# io-pack-3-4.net
KiCad netlist of a schematic drawn in EAGLE
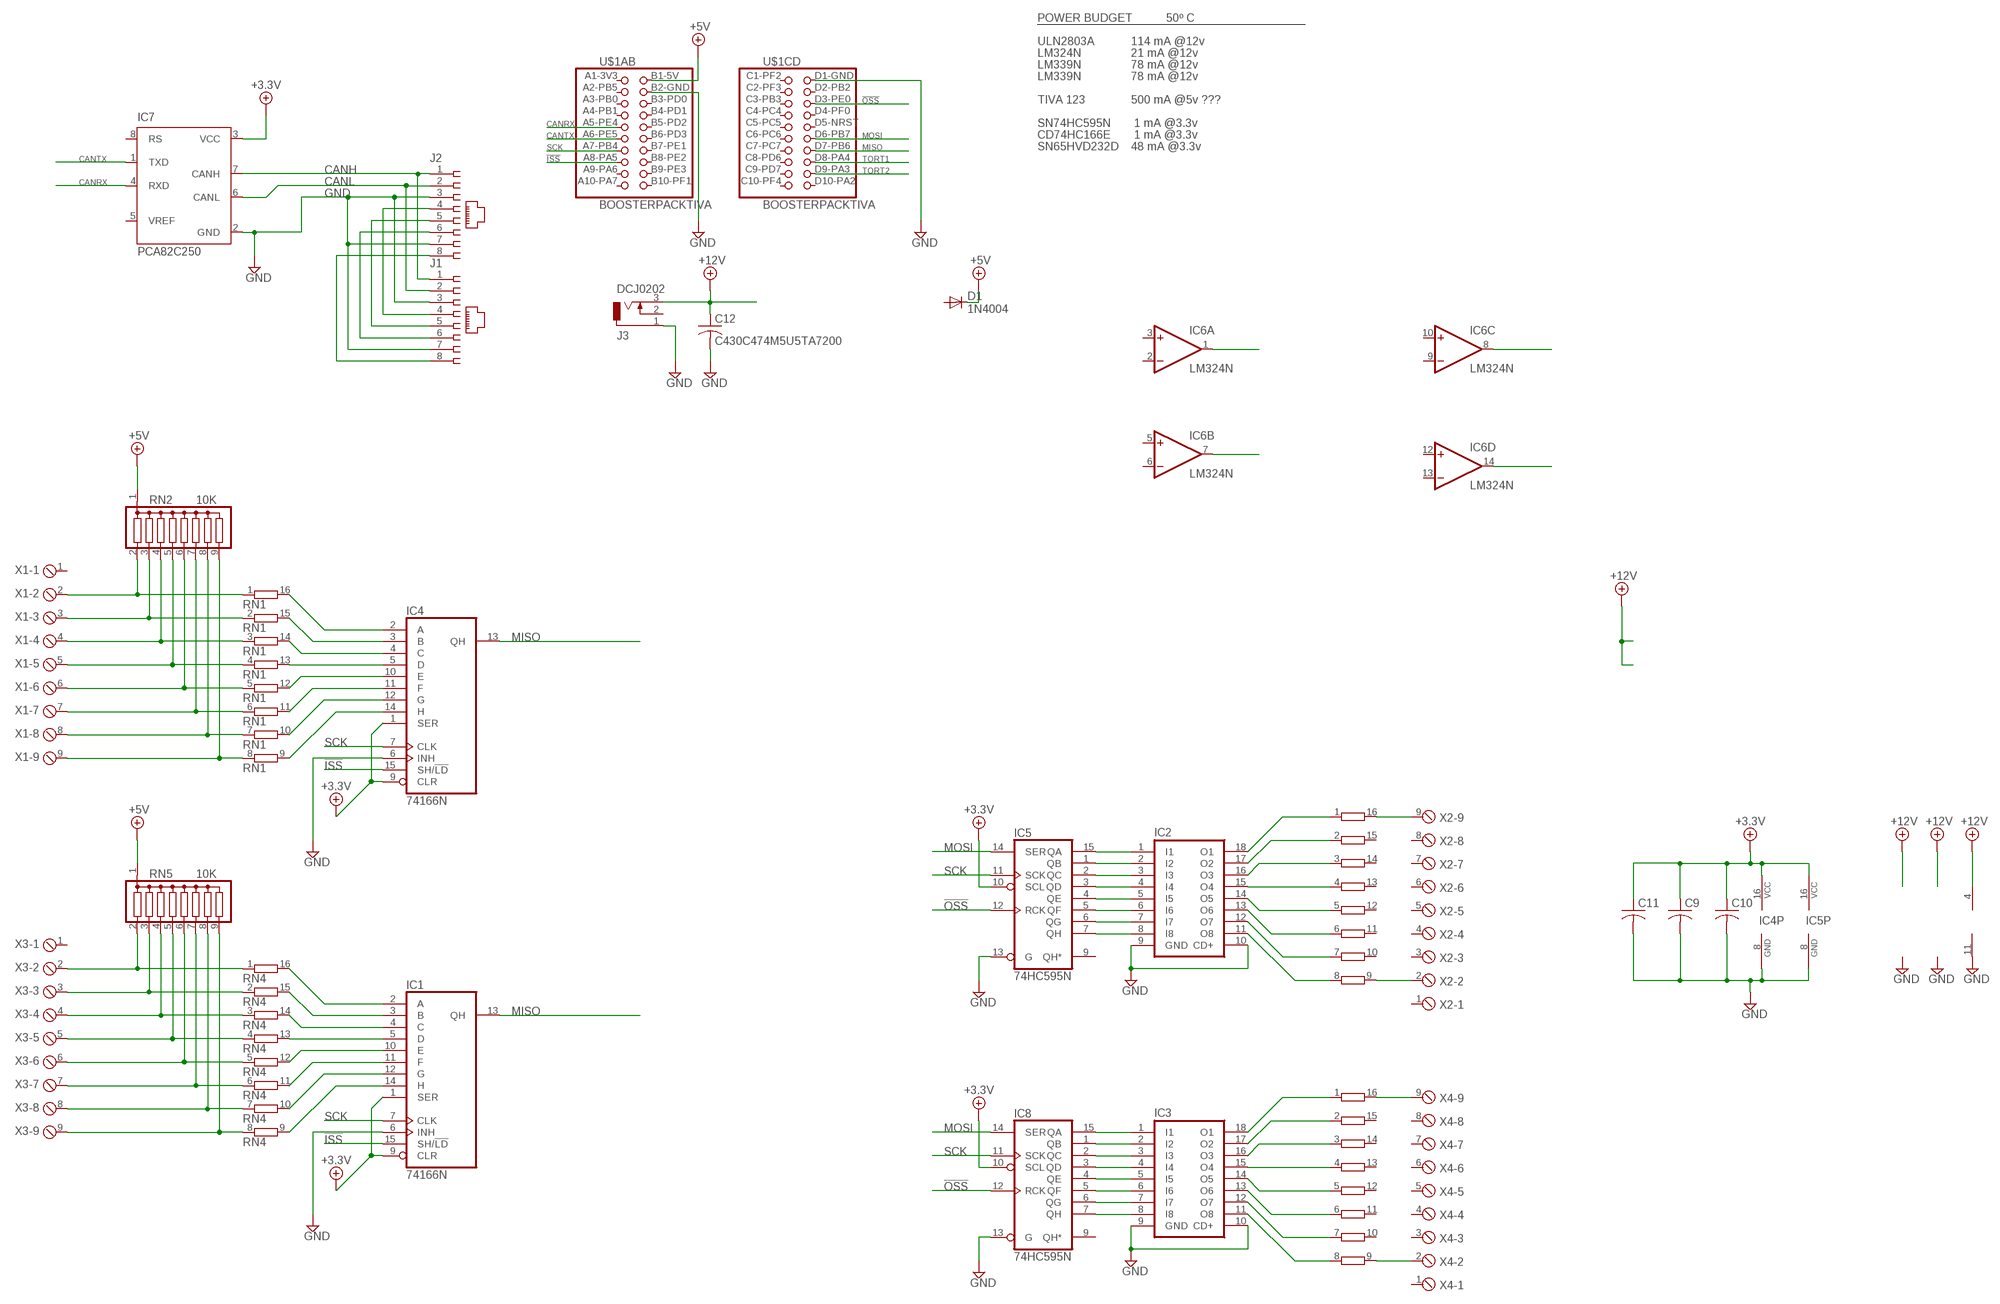
[diagram p0: schematic, sheet 1]

(export (version "E")
  (design (tool "Eeschema 10.0.6"))
  (components
    (comp (ref "C9")
      (value "C-US050-025X075")
      (footprint "eagle-import:C050-025X075")
      (libsource (lib "eagle-import") (part "C-US050-025X075"))
    )
    (comp (ref "C10")
      (value "C-US050-025X075")
      (footprint "eagle-import:C050-025X075")
      (libsource (lib "eagle-import") (part "C-US050-025X075"))
    )
    (comp (ref "C11")
      (value "C-US050-025X075")
      (footprint "eagle-import:C050-025X075")
      (libsource (lib "eagle-import") (part "C-US050-025X075"))
    )
    (comp (ref "C12")
      (value "C430C474M5U5TA7200")
      (footprint "eagle-import:C075-032X103")
      (libsource (lib "eagle-import") (part "C-US075-032X103"))
    )
    (comp (ref "D1")
      (value "1N4004")
      (footprint "eagle-import:DO41-10")
      (libsource (lib "eagle-import") (part "1N4004"))
    )
    (comp (ref "IC1")
      (value "74166N")
      (footprint "eagle-import:DIL16")
      (libsource (lib "eagle-import") (part "74166N"))
    )
    (comp (ref "IC2")
      (value "ULN2803A")
      (footprint "eagle-import:DIL18")
      (libsource (lib "eagle-import") (part "ULN2803A"))
    )
    (comp (ref "IC3")
      (value "ULN2803A")
      (footprint "eagle-import:DIL18")
      (libsource (lib "eagle-import") (part "ULN2803A"))
    )
    (comp (ref "IC4")
      (value "74166N")
      (footprint "eagle-import:DIL16")
      (libsource (lib "eagle-import") (part "74166N"))
    )
    (comp (ref "IC5")
      (value "74HC595N")
      (footprint "eagle-import:DIL16")
      (libsource (lib "eagle-import") (part "74595NLS"))
    )
    (comp (ref "IC6")
      (value "LM324N")
      (footprint "eagle-import:DIL14")
      (libsource (lib "eagle-import") (part "LM324N"))
    )
    (comp (ref "IC7")
      (value "PCA82C250")
      (footprint "eagle-import:DIL08")
      (libsource (lib "eagle-import") (part "PCA82C250"))
    )
    (comp (ref "IC8")
      (value "74HC595N")
      (footprint "eagle-import:DIL16")
      (libsource (lib "eagle-import") (part "74595NLS"))
    )
    (comp (ref "J1")
      (value "555164-1")
      (footprint "eagle-import:555164-1")
      (libsource (lib "eagle-import") (part "555164-1"))
    )
    (comp (ref "J2")
      (value "555164-1")
      (footprint "eagle-import:555164-1")
      (libsource (lib "eagle-import") (part "555164-1"))
    )
    (comp (ref "J3")
      (value "DCJ0202")
      (footprint "eagle-import:DCJ0202")
      (libsource (lib "eagle-import") (part "DCJ0202"))
    )
    (comp (ref "RN1")
      (value "8R-P")
      (footprint "eagle-import:DIL16")
      (libsource (lib "eagle-import") (part "8R-P"))
    )
    (comp (ref "RN2")
      (value "10K")
      (footprint "eagle-import:SIL9")
      (libsource (lib "eagle-import") (part "G08R"))
    )
    (comp (ref "RN3")
      (value "8R-P")
      (footprint "eagle-import:DIL16")
      (libsource (lib "eagle-import") (part "8R-P"))
    )
    (comp (ref "RN4")
      (value "8R-P")
      (footprint "eagle-import:DIL16")
      (libsource (lib "eagle-import") (part "8R-P"))
    )
    (comp (ref "RN5")
      (value "10K")
      (footprint "eagle-import:SIL9")
      (libsource (lib "eagle-import") (part "G08R"))
    )
    (comp (ref "RN6")
      (value "8R-P")
      (footprint "eagle-import:DIL16")
      (libsource (lib "eagle-import") (part "8R-P"))
    )
    (comp (ref "U$1")
      (value "BOOSTERPACKTIVA")
      (footprint "eagle-import:BOOSTERPACK-TIVA")
      (libsource (lib "eagle-import") (part "BOOSTERPACKTIVA"))
    )
    (comp (ref "X1")
      (value "MPT9")
      (footprint "eagle-import:9POL254")
      (libsource (lib "eagle-import") (part "MPT9"))
    )
    (comp (ref "X2")
      (value "MPT9")
      (footprint "eagle-import:9POL254")
      (libsource (lib "eagle-import") (part "MPT9"))
    )
    (comp (ref "X3")
      (value "MPT9")
      (footprint "eagle-import:9POL254")
      (libsource (lib "eagle-import") (part "MPT9"))
    )
    (comp (ref "X4")
      (value "MPT9")
      (footprint "eagle-import:9POL254")
      (libsource (lib "eagle-import") (part "MPT9"))
    )
  )
  (nets
    (net (code "1") (name "+3.3V") (class "Default")
      (node (ref "C10") (pin "1") (pinfunction "1_1") (pintype "passive"))
      (node (ref "C11") (pin "1") (pinfunction "1_1") (pintype "passive"))
      (node (ref "C9") (pin "1") (pinfunction "1_1") (pintype "passive"))
      (node (ref "IC1") (pin "1") (pinfunction "SER_1") (pintype "input"))
      (node (ref "IC1") (pin "9") (pinfunction "CLR_9") (pintype "input"))
      (node (ref "IC4") (pin "1") (pinfunction "SER_1") (pintype "input"))
      (node (ref "IC4") (pin "16") (pinfunction "VCC_16") (pintype "power_in"))
      (node (ref "IC4") (pin "9") (pinfunction "CLR_9") (pintype "input"))
      (node (ref "IC5") (pin "10") (pinfunction "SCL_10") (pintype "input"))
      (node (ref "IC5") (pin "16") (pinfunction "VCC_16") (pintype "power_in"))
      (node (ref "IC7") (pin "3") (pinfunction "VCC_3") (pintype "power_in"))
      (node (ref "IC8") (pin "10") (pinfunction "SCL_10") (pintype "input"))
    )
    (net (code "2") (name "+5V") (class "Default")
      (node (ref "D1") (pin "C") (pinfunction "C_C") (pintype "passive"))
      (node (ref "RN2") (pin "1") (pinfunction "1_1") (pintype "passive"))
      (node (ref "RN5") (pin "1") (pinfunction "1_1") (pintype "passive"))
      (node (ref "U$1") (pin "B1-5V") (pinfunction "2_B1-5V") (pintype "passive"))
    )
    (net (code "3") (name "+12V") (class "Default")
      (node (ref "C12") (pin "1") (pinfunction "1_1") (pintype "passive"))
      (node (ref "IC6") (pin "4") (pinfunction "V+_4") (pintype "power_in"))
      (node (ref "J3") (pin "3") (pinfunction "3_3") (pintype "passive"))
    )
    (net (code "4") (name "/CANH") (class "Default")
      (node (ref "IC7") (pin "7") (pinfunction "CANH_7") (pintype "bidirectional"))
      (node (ref "J1") (pin "1") (pinfunction "1_1") (pintype "passive"))
      (node (ref "J2") (pin "1") (pinfunction "1_1") (pintype "passive"))
    )
    (net (code "5") (name "/CANL") (class "Default")
      (node (ref "IC7") (pin "6") (pinfunction "CANL_6") (pintype "bidirectional"))
      (node (ref "J1") (pin "2") (pinfunction "2_2") (pintype "passive"))
      (node (ref "J2") (pin "2") (pinfunction "2_2") (pintype "passive"))
    )
    (net (code "6") (name "/CANRX") (class "Default")
      (node (ref "IC7") (pin "4") (pinfunction "RXD_4") (pintype "output"))
      (node (ref "U$1") (pin "A5-PE4") (pinfunction "9_A5-PE4") (pintype "passive"))
    )
    (net (code "7") (name "/CANTX") (class "Default")
      (node (ref "IC7") (pin "1") (pinfunction "TXD_1") (pintype "input"))
      (node (ref "U$1") (pin "A6-PE5") (pinfunction "11_A6-PE5") (pintype "passive"))
    )
    (net (code "8") (name "/MISO") (class "Default")
      (node (ref "IC1") (pin "13") (pinfunction "QH_13") (pintype "output"))
      (node (ref "IC4") (pin "13") (pinfunction "QH_13") (pintype "output"))
      (node (ref "U$1") (pin "D7-PB6") (pinfunction "14_D7-PB6") (pintype "passive"))
    )
    (net (code "9") (name "/MOSI") (class "Default")
      (node (ref "IC5") (pin "14") (pinfunction "SER_14") (pintype "input"))
      (node (ref "IC8") (pin "14") (pinfunction "SER_14") (pintype "input"))
      (node (ref "U$1") (pin "D6-PB7") (pinfunction "12_D6-PB7") (pintype "passive"))
    )
    (net (code "10") (name "/SCK") (class "Default")
      (node (ref "IC1") (pin "7") (pinfunction "CLK_7") (pintype "input"))
      (node (ref "IC4") (pin "7") (pinfunction "CLK_7") (pintype "input"))
      (node (ref "IC5") (pin "11") (pinfunction "SCK_11") (pintype "input"))
      (node (ref "IC8") (pin "11") (pinfunction "SCK_11") (pintype "input"))
      (node (ref "U$1") (pin "A7-PB4") (pinfunction "13_A7-PB4") (pintype "passive"))
    )
    (net (code "11") (name "/TORT1") (class "Default")
      (node (ref "U$1") (pin "D8-PA4") (pinfunction "16_D8-PA4") (pintype "passive"))
    )
    (net (code "12") (name "/TORT2") (class "Default")
      (node (ref "U$1") (pin "D9-PA3") (pinfunction "18_D9-PA3") (pintype "passive"))
    )
    (net (code "13") (name "/~{ISS}") (class "Default")
      (node (ref "IC1") (pin "15") (pinfunction "SH/~{LD}_15") (pintype "input"))
      (node (ref "IC4") (pin "15") (pinfunction "SH/~{LD}_15") (pintype "input"))
      (node (ref "U$1") (pin "A8-PA5") (pinfunction "15_A8-PA5") (pintype "passive"))
    )
    (net (code "14") (name "/~{OSS}") (class "Default")
      (node (ref "IC5") (pin "12") (pinfunction "RCK_12") (pintype "input"))
      (node (ref "IC8") (pin "12") (pinfunction "RCK_12") (pintype "input"))
      (node (ref "U$1") (pin "D3-PE0") (pinfunction "6_D3-PE0") (pintype "passive"))
    )
    (net (code "15") (name "GND") (class "Default")
      (node (ref "C10") (pin "2") (pinfunction "2_2") (pintype "passive"))
      (node (ref "C11") (pin "2") (pinfunction "2_2") (pintype "passive"))
      (node (ref "C12") (pin "2") (pinfunction "2_2") (pintype "passive"))
      (node (ref "C9") (pin "2") (pinfunction "2_2") (pintype "passive"))
      (node (ref "IC1") (pin "6") (pinfunction "INH_6") (pintype "input"))
      (node (ref "IC2") (pin "10") (pinfunction "CD+_10") (pintype "passive"))
      (node (ref "IC2") (pin "9") (pinfunction "GND_9") (pintype "power_in"))
      (node (ref "IC3") (pin "10") (pinfunction "CD+_10") (pintype "passive"))
      (node (ref "IC3") (pin "9") (pinfunction "GND_9") (pintype "power_in"))
      (node (ref "IC4") (pin "6") (pinfunction "INH_6") (pintype "input"))
      (node (ref "IC4") (pin "8") (pinfunction "GND_8") (pintype "power_in"))
      (node (ref "IC5") (pin "13") (pinfunction "G_13") (pintype "input"))
      (node (ref "IC5") (pin "8") (pinfunction "GND_8") (pintype "power_in"))
      (node (ref "IC6") (pin "11") (pinfunction "V-_11") (pintype "power_in"))
      (node (ref "IC7") (pin "2") (pinfunction "GND_2") (pintype "power_in"))
      (node (ref "IC8") (pin "13") (pinfunction "G_13") (pintype "input"))
      (node (ref "J1") (pin "3") (pinfunction "3_3") (pintype "passive"))
      (node (ref "J1") (pin "7") (pinfunction "7_7") (pintype "passive"))
      (node (ref "J2") (pin "3") (pinfunction "3_3") (pintype "passive"))
      (node (ref "J2") (pin "7") (pinfunction "7_7") (pintype "passive"))
      (node (ref "J3") (pin "1") (pinfunction "1_1") (pintype "passive"))
      (node (ref "U$1") (pin "B2-GND") (pinfunction "4_B2-GND") (pintype "passive"))
      (node (ref "U$1") (pin "D1-GND") (pinfunction "2_D1-GND") (pintype "passive"))
    )
    (net (code "16") (name "Net-(IC1A-A)") (class "Default")
      (node (ref "IC1") (pin "2") (pinfunction "A_2") (pintype "input"))
      (node (ref "RN4") (pin "16") (pinfunction "2_16") (pintype "passive"))
    )
    (net (code "17") (name "Net-(IC1A-B)") (class "Default")
      (node (ref "IC1") (pin "3") (pinfunction "B_3") (pintype "input"))
      (node (ref "RN4") (pin "15") (pinfunction "2_15") (pintype "passive"))
    )
    (net (code "18") (name "Net-(IC1A-C)") (class "Default")
      (node (ref "IC1") (pin "4") (pinfunction "C_4") (pintype "input"))
      (node (ref "RN4") (pin "14") (pinfunction "2_14") (pintype "passive"))
    )
    (net (code "19") (name "Net-(IC1A-D)") (class "Default")
      (node (ref "IC1") (pin "5") (pinfunction "D_5") (pintype "input"))
      (node (ref "RN4") (pin "13") (pinfunction "2_13") (pintype "passive"))
    )
    (net (code "20") (name "Net-(IC1A-E)") (class "Default")
      (node (ref "IC1") (pin "10") (pinfunction "E_10") (pintype "input"))
      (node (ref "RN4") (pin "12") (pinfunction "2_12") (pintype "passive"))
    )
    (net (code "21") (name "Net-(IC1A-F)") (class "Default")
      (node (ref "IC1") (pin "11") (pinfunction "F_11") (pintype "input"))
      (node (ref "RN4") (pin "11") (pinfunction "2_11") (pintype "passive"))
    )
    (net (code "22") (name "Net-(IC1A-G)") (class "Default")
      (node (ref "IC1") (pin "12") (pinfunction "G_12") (pintype "input"))
      (node (ref "RN4") (pin "10") (pinfunction "2_10") (pintype "passive"))
    )
    (net (code "23") (name "Net-(IC1A-H)") (class "Default")
      (node (ref "IC1") (pin "14") (pinfunction "H_14") (pintype "input"))
      (node (ref "RN4") (pin "9") (pinfunction "2_9") (pintype "passive"))
    )
    (net (code "24") (name "Net-(IC2-I1)") (class "Default")
      (node (ref "IC2") (pin "1") (pinfunction "I1_1") (pintype "input"))
      (node (ref "IC5") (pin "15") (pinfunction "QA_15") (pintype "tri_state"))
    )
    (net (code "25") (name "Net-(IC2-I2)") (class "Default")
      (node (ref "IC2") (pin "2") (pinfunction "I2_2") (pintype "input"))
      (node (ref "IC5") (pin "1") (pinfunction "QB_1") (pintype "tri_state"))
    )
    (net (code "26") (name "Net-(IC2-I3)") (class "Default")
      (node (ref "IC2") (pin "3") (pinfunction "I3_3") (pintype "input"))
      (node (ref "IC5") (pin "2") (pinfunction "QC_2") (pintype "tri_state"))
    )
    (net (code "27") (name "Net-(IC2-I4)") (class "Default")
      (node (ref "IC2") (pin "4") (pinfunction "I4_4") (pintype "input"))
      (node (ref "IC5") (pin "3") (pinfunction "QD_3") (pintype "tri_state"))
    )
    (net (code "28") (name "Net-(IC2-I5)") (class "Default")
      (node (ref "IC2") (pin "5") (pinfunction "I5_5") (pintype "input"))
      (node (ref "IC5") (pin "4") (pinfunction "QE_4") (pintype "tri_state"))
    )
    (net (code "29") (name "Net-(IC2-I6)") (class "Default")
      (node (ref "IC2") (pin "6") (pinfunction "I6_6") (pintype "input"))
      (node (ref "IC5") (pin "5") (pinfunction "QF_5") (pintype "tri_state"))
    )
    (net (code "30") (name "Net-(IC2-I7)") (class "Default")
      (node (ref "IC2") (pin "7") (pinfunction "I7_7") (pintype "input"))
      (node (ref "IC5") (pin "6") (pinfunction "QG_6") (pintype "tri_state"))
    )
    (net (code "31") (name "Net-(IC2-I8)") (class "Default")
      (node (ref "IC2") (pin "8") (pinfunction "I8_8") (pintype "input"))
      (node (ref "IC5") (pin "7") (pinfunction "QH_7") (pintype "tri_state"))
    )
    (net (code "32") (name "Net-(IC2-O1)") (class "Default")
      (node (ref "IC2") (pin "18") (pinfunction "O1_18") (pintype "open_collector"))
      (node (ref "RN3") (pin "1") (pinfunction "1_1") (pintype "passive"))
    )
    (net (code "33") (name "Net-(IC2-O2)") (class "Default")
      (node (ref "IC2") (pin "17") (pinfunction "O2_17") (pintype "open_collector"))
      (node (ref "RN3") (pin "2") (pinfunction "1_2") (pintype "passive"))
    )
    (net (code "34") (name "Net-(IC2-O3)") (class "Default")
      (node (ref "IC2") (pin "16") (pinfunction "O3_16") (pintype "open_collector"))
      (node (ref "RN3") (pin "3") (pinfunction "1_3") (pintype "passive"))
    )
    (net (code "35") (name "Net-(IC2-O4)") (class "Default")
      (node (ref "IC2") (pin "15") (pinfunction "O4_15") (pintype "open_collector"))
      (node (ref "RN3") (pin "4") (pinfunction "1_4") (pintype "passive"))
    )
    (net (code "36") (name "Net-(IC2-O5)") (class "Default")
      (node (ref "IC2") (pin "14") (pinfunction "O5_14") (pintype "open_collector"))
      (node (ref "RN3") (pin "5") (pinfunction "1_5") (pintype "passive"))
    )
    (net (code "37") (name "Net-(IC2-O6)") (class "Default")
      (node (ref "IC2") (pin "13") (pinfunction "O6_13") (pintype "open_collector"))
      (node (ref "RN3") (pin "6") (pinfunction "1_6") (pintype "passive"))
    )
    (net (code "38") (name "Net-(IC2-O7)") (class "Default")
      (node (ref "IC2") (pin "12") (pinfunction "O7_12") (pintype "open_collector"))
      (node (ref "RN3") (pin "7") (pinfunction "1_7") (pintype "passive"))
    )
    (net (code "39") (name "Net-(IC2-O8)") (class "Default")
      (node (ref "IC2") (pin "11") (pinfunction "O8_11") (pintype "open_collector"))
      (node (ref "RN3") (pin "8") (pinfunction "1_8") (pintype "passive"))
    )
    (net (code "40") (name "Net-(IC3-I1)") (class "Default")
      (node (ref "IC3") (pin "1") (pinfunction "I1_1") (pintype "input"))
      (node (ref "IC8") (pin "15") (pinfunction "QA_15") (pintype "tri_state"))
    )
    (net (code "41") (name "Net-(IC3-I2)") (class "Default")
      (node (ref "IC3") (pin "2") (pinfunction "I2_2") (pintype "input"))
      (node (ref "IC8") (pin "1") (pinfunction "QB_1") (pintype "tri_state"))
    )
    (net (code "42") (name "Net-(IC3-I3)") (class "Default")
      (node (ref "IC3") (pin "3") (pinfunction "I3_3") (pintype "input"))
      (node (ref "IC8") (pin "2") (pinfunction "QC_2") (pintype "tri_state"))
    )
    (net (code "43") (name "Net-(IC3-I4)") (class "Default")
      (node (ref "IC3") (pin "4") (pinfunction "I4_4") (pintype "input"))
      (node (ref "IC8") (pin "3") (pinfunction "QD_3") (pintype "tri_state"))
    )
    (net (code "44") (name "Net-(IC3-I5)") (class "Default")
      (node (ref "IC3") (pin "5") (pinfunction "I5_5") (pintype "input"))
      (node (ref "IC8") (pin "4") (pinfunction "QE_4") (pintype "tri_state"))
    )
    (net (code "45") (name "Net-(IC3-I6)") (class "Default")
      (node (ref "IC3") (pin "6") (pinfunction "I6_6") (pintype "input"))
      (node (ref "IC8") (pin "5") (pinfunction "QF_5") (pintype "tri_state"))
    )
    (net (code "46") (name "Net-(IC3-I7)") (class "Default")
      (node (ref "IC3") (pin "7") (pinfunction "I7_7") (pintype "input"))
      (node (ref "IC8") (pin "6") (pinfunction "QG_6") (pintype "tri_state"))
    )
    (net (code "47") (name "Net-(IC3-I8)") (class "Default")
      (node (ref "IC3") (pin "8") (pinfunction "I8_8") (pintype "input"))
      (node (ref "IC8") (pin "7") (pinfunction "QH_7") (pintype "tri_state"))
    )
    (net (code "48") (name "Net-(IC3-O1)") (class "Default")
      (node (ref "IC3") (pin "18") (pinfunction "O1_18") (pintype "open_collector"))
      (node (ref "RN6") (pin "1") (pinfunction "1_1") (pintype "passive"))
    )
    (net (code "49") (name "Net-(IC3-O2)") (class "Default")
      (node (ref "IC3") (pin "17") (pinfunction "O2_17") (pintype "open_collector"))
      (node (ref "RN6") (pin "2") (pinfunction "1_2") (pintype "passive"))
    )
    (net (code "50") (name "Net-(IC3-O3)") (class "Default")
      (node (ref "IC3") (pin "16") (pinfunction "O3_16") (pintype "open_collector"))
      (node (ref "RN6") (pin "3") (pinfunction "1_3") (pintype "passive"))
    )
    (net (code "51") (name "Net-(IC3-O4)") (class "Default")
      (node (ref "IC3") (pin "15") (pinfunction "O4_15") (pintype "open_collector"))
      (node (ref "RN6") (pin "4") (pinfunction "1_4") (pintype "passive"))
    )
    (net (code "52") (name "Net-(IC3-O5)") (class "Default")
      (node (ref "IC3") (pin "14") (pinfunction "O5_14") (pintype "open_collector"))
      (node (ref "RN6") (pin "5") (pinfunction "1_5") (pintype "passive"))
    )
    (net (code "53") (name "Net-(IC3-O6)") (class "Default")
      (node (ref "IC3") (pin "13") (pinfunction "O6_13") (pintype "open_collector"))
      (node (ref "RN6") (pin "6") (pinfunction "1_6") (pintype "passive"))
    )
    (net (code "54") (name "Net-(IC3-O7)") (class "Default")
      (node (ref "IC3") (pin "12") (pinfunction "O7_12") (pintype "open_collector"))
      (node (ref "RN6") (pin "7") (pinfunction "1_7") (pintype "passive"))
    )
    (net (code "55") (name "Net-(IC3-O8)") (class "Default")
      (node (ref "IC3") (pin "11") (pinfunction "O8_11") (pintype "open_collector"))
      (node (ref "RN6") (pin "8") (pinfunction "1_8") (pintype "passive"))
    )
    (net (code "56") (name "Net-(IC4A-A)") (class "Default")
      (node (ref "IC4") (pin "2") (pinfunction "A_2") (pintype "input"))
      (node (ref "RN1") (pin "16") (pinfunction "2_16") (pintype "passive"))
    )
    (net (code "57") (name "Net-(IC4A-B)") (class "Default")
      (node (ref "IC4") (pin "3") (pinfunction "B_3") (pintype "input"))
      (node (ref "RN1") (pin "15") (pinfunction "2_15") (pintype "passive"))
    )
    (net (code "58") (name "Net-(IC4A-C)") (class "Default")
      (node (ref "IC4") (pin "4") (pinfunction "C_4") (pintype "input"))
      (node (ref "RN1") (pin "14") (pinfunction "2_14") (pintype "passive"))
    )
    (net (code "59") (name "Net-(IC4A-D)") (class "Default")
      (node (ref "IC4") (pin "5") (pinfunction "D_5") (pintype "input"))
      (node (ref "RN1") (pin "13") (pinfunction "2_13") (pintype "passive"))
    )
    (net (code "60") (name "Net-(IC4A-E)") (class "Default")
      (node (ref "IC4") (pin "10") (pinfunction "E_10") (pintype "input"))
      (node (ref "RN1") (pin "12") (pinfunction "2_12") (pintype "passive"))
    )
    (net (code "61") (name "Net-(IC4A-F)") (class "Default")
      (node (ref "IC4") (pin "11") (pinfunction "F_11") (pintype "input"))
      (node (ref "RN1") (pin "11") (pinfunction "2_11") (pintype "passive"))
    )
    (net (code "62") (name "Net-(IC4A-G)") (class "Default")
      (node (ref "IC4") (pin "12") (pinfunction "G_12") (pintype "input"))
      (node (ref "RN1") (pin "10") (pinfunction "2_10") (pintype "passive"))
    )
    (net (code "63") (name "Net-(IC4A-H)") (class "Default")
      (node (ref "IC4") (pin "14") (pinfunction "H_14") (pintype "input"))
      (node (ref "RN1") (pin "9") (pinfunction "2_9") (pintype "passive"))
    )
    (net (code "64") (name "Net-(J1-Pad4)") (class "Default")
      (node (ref "J1") (pin "4") (pinfunction "4_4") (pintype "passive"))
      (node (ref "J2") (pin "4") (pinfunction "4_4") (pintype "passive"))
    )
    (net (code "65") (name "Net-(J1-Pad5)") (class "Default")
      (node (ref "J1") (pin "5") (pinfunction "5_5") (pintype "passive"))
      (node (ref "J2") (pin "5") (pinfunction "5_5") (pintype "passive"))
    )
    (net (code "66") (name "Net-(J1-Pad6)") (class "Default")
      (node (ref "J1") (pin "6") (pinfunction "6_6") (pintype "passive"))
      (node (ref "J2") (pin "6") (pinfunction "6_6") (pintype "passive"))
    )
    (net (code "67") (name "Net-(J1-Pad8)") (class "Default")
      (node (ref "J1") (pin "8") (pinfunction "8_8") (pintype "passive"))
      (node (ref "J2") (pin "8") (pinfunction "8_8") (pintype "passive"))
    )
    (net (code "68") (name "Net-(RN1B-1)") (class "Default")
      (node (ref "RN1") (pin "2") (pinfunction "1_2") (pintype "passive"))
      (node (ref "RN2") (pin "3") (pinfunction "3_3") (pintype "passive"))
      (node (ref "X1") (pin "3") (pinfunction "1_3") (pintype "passive"))
    )
    (net (code "69") (name "Net-(RN1C-1)") (class "Default")
      (node (ref "RN1") (pin "3") (pinfunction "1_3") (pintype "passive"))
      (node (ref "RN2") (pin "4") (pinfunction "4_4") (pintype "passive"))
      (node (ref "X1") (pin "4") (pinfunction "1_4") (pintype "passive"))
    )
    (net (code "70") (name "Net-(RN1D-1)") (class "Default")
      (node (ref "RN1") (pin "4") (pinfunction "1_4") (pintype "passive"))
      (node (ref "RN2") (pin "5") (pinfunction "5_5") (pintype "passive"))
      (node (ref "X1") (pin "5") (pinfunction "1_5") (pintype "passive"))
    )
    (net (code "71") (name "Net-(RN1E-1)") (class "Default")
      (node (ref "RN1") (pin "5") (pinfunction "1_5") (pintype "passive"))
      (node (ref "RN2") (pin "6") (pinfunction "6_6") (pintype "passive"))
      (node (ref "X1") (pin "6") (pinfunction "1_6") (pintype "passive"))
    )
    (net (code "72") (name "Net-(RN1F-1)") (class "Default")
      (node (ref "RN1") (pin "6") (pinfunction "1_6") (pintype "passive"))
      (node (ref "RN2") (pin "7") (pinfunction "7_7") (pintype "passive"))
      (node (ref "X1") (pin "7") (pinfunction "1_7") (pintype "passive"))
    )
    (net (code "73") (name "Net-(RN1G-1)") (class "Default")
      (node (ref "RN1") (pin "7") (pinfunction "1_7") (pintype "passive"))
      (node (ref "RN2") (pin "8") (pinfunction "8_8") (pintype "passive"))
      (node (ref "X1") (pin "8") (pinfunction "1_8") (pintype "passive"))
    )
    (net (code "74") (name "Net-(RN1H-1)") (class "Default")
      (node (ref "RN1") (pin "8") (pinfunction "1_8") (pintype "passive"))
      (node (ref "RN2") (pin "9") (pinfunction "9_9") (pintype "passive"))
      (node (ref "X1") (pin "9") (pinfunction "1_9") (pintype "passive"))
    )
    (net (code "75") (name "Net-(RN3A-2)") (class "Default")
      (node (ref "RN3") (pin "16") (pinfunction "2_16") (pintype "passive"))
      (node (ref "X2") (pin "9") (pinfunction "1_9") (pintype "passive"))
    )
    (net (code "76") (name "Net-(RN3H-2)") (class "Default")
      (node (ref "RN3") (pin "9") (pinfunction "2_9") (pintype "passive"))
      (node (ref "X2") (pin "2") (pinfunction "1_2") (pintype "passive"))
    )
    (net (code "77") (name "Net-(RN4B-1)") (class "Default")
      (node (ref "RN4") (pin "2") (pinfunction "1_2") (pintype "passive"))
      (node (ref "RN5") (pin "3") (pinfunction "3_3") (pintype "passive"))
      (node (ref "X3") (pin "3") (pinfunction "1_3") (pintype "passive"))
    )
    (net (code "78") (name "Net-(RN4C-1)") (class "Default")
      (node (ref "RN4") (pin "3") (pinfunction "1_3") (pintype "passive"))
      (node (ref "RN5") (pin "4") (pinfunction "4_4") (pintype "passive"))
      (node (ref "X3") (pin "4") (pinfunction "1_4") (pintype "passive"))
    )
    (net (code "79") (name "Net-(RN4D-1)") (class "Default")
      (node (ref "RN4") (pin "4") (pinfunction "1_4") (pintype "passive"))
      (node (ref "RN5") (pin "5") (pinfunction "5_5") (pintype "passive"))
      (node (ref "X3") (pin "5") (pinfunction "1_5") (pintype "passive"))
    )
    (net (code "80") (name "Net-(RN4E-1)") (class "Default")
      (node (ref "RN4") (pin "5") (pinfunction "1_5") (pintype "passive"))
      (node (ref "RN5") (pin "6") (pinfunction "6_6") (pintype "passive"))
      (node (ref "X3") (pin "6") (pinfunction "1_6") (pintype "passive"))
    )
    (net (code "81") (name "Net-(RN4F-1)") (class "Default")
      (node (ref "RN4") (pin "6") (pinfunction "1_6") (pintype "passive"))
      (node (ref "RN5") (pin "7") (pinfunction "7_7") (pintype "passive"))
      (node (ref "X3") (pin "7") (pinfunction "1_7") (pintype "passive"))
    )
    (net (code "82") (name "Net-(RN4G-1)") (class "Default")
      (node (ref "RN4") (pin "7") (pinfunction "1_7") (pintype "passive"))
      (node (ref "RN5") (pin "8") (pinfunction "8_8") (pintype "passive"))
      (node (ref "X3") (pin "8") (pinfunction "1_8") (pintype "passive"))
    )
    (net (code "83") (name "Net-(RN4H-1)") (class "Default")
      (node (ref "RN4") (pin "8") (pinfunction "1_8") (pintype "passive"))
      (node (ref "RN5") (pin "9") (pinfunction "9_9") (pintype "passive"))
      (node (ref "X3") (pin "9") (pinfunction "1_9") (pintype "passive"))
    )
    (net (code "84") (name "Net-(RN6A-2)") (class "Default")
      (node (ref "RN6") (pin "16") (pinfunction "2_16") (pintype "passive"))
      (node (ref "X4") (pin "9") (pinfunction "1_9") (pintype "passive"))
    )
    (net (code "85") (name "Net-(RN6H-2)") (class "Default")
      (node (ref "RN6") (pin "9") (pinfunction "2_9") (pintype "passive"))
      (node (ref "X4") (pin "2") (pinfunction "1_2") (pintype "passive"))
    )
    (net (code "86") (name "Net-(X1B-1)") (class "Default")
      (node (ref "RN1") (pin "1") (pinfunction "1_1") (pintype "passive"))
      (node (ref "RN2") (pin "2") (pinfunction "2_2") (pintype "passive"))
      (node (ref "X1") (pin "2") (pinfunction "1_2") (pintype "passive"))
    )
    (net (code "87") (name "Net-(X3B-1)") (class "Default")
      (node (ref "RN4") (pin "1") (pinfunction "1_1") (pintype "passive"))
      (node (ref "RN5") (pin "2") (pinfunction "2_2") (pintype "passive"))
      (node (ref "X3") (pin "2") (pinfunction "1_2") (pintype "passive"))
    )
    (net (code "88") (name "unconnected-(D1-PadA)") (class "Default")
      (node (ref "D1") (pin "A") (pinfunction "A_A") (pintype "passive"))
    )
    (net (code "89") (name "unconnected-(IC5A-QH*-Pad9)") (class "Default")
      (node (ref "IC5") (pin "9") (pinfunction "QH*_9") (pintype "tri_state"))
    )
    (net (code "90") (name "unconnected-(IC6A-+IN-Pad3)") (class "Default")
      (node (ref "IC6") (pin "3") (pinfunction "+IN_3") (pintype "input"))
    )
    (net (code "91") (name "unconnected-(IC6A--IN-Pad2)") (class "Default")
      (node (ref "IC6") (pin "2") (pinfunction "-IN_2") (pintype "input"))
    )
    (net (code "92") (name "unconnected-(IC6A-OUT-Pad1)") (class "Default")
      (node (ref "IC6") (pin "1") (pinfunction "OUT_1") (pintype "output"))
    )
    (net (code "93") (name "unconnected-(IC6B-+IN-Pad5)") (class "Default")
      (node (ref "IC6") (pin "5") (pinfunction "+IN_5") (pintype "input"))
    )
    (net (code "94") (name "unconnected-(IC6B--IN-Pad6)") (class "Default")
      (node (ref "IC6") (pin "6") (pinfunction "-IN_6") (pintype "input"))
    )
    (net (code "95") (name "unconnected-(IC6B-OUT-Pad7)") (class "Default")
      (node (ref "IC6") (pin "7") (pinfunction "OUT_7") (pintype "output"))
    )
    (net (code "96") (name "unconnected-(IC6C-+IN-Pad10)") (class "Default")
      (node (ref "IC6") (pin "10") (pinfunction "+IN_10") (pintype "input"))
    )
    (net (code "97") (name "unconnected-(IC6C--IN-Pad9)") (class "Default")
      (node (ref "IC6") (pin "9") (pinfunction "-IN_9") (pintype "input"))
    )
    (net (code "98") (name "unconnected-(IC6C-OUT-Pad8)") (class "Default")
      (node (ref "IC6") (pin "8") (pinfunction "OUT_8") (pintype "output"))
    )
    (net (code "99") (name "unconnected-(IC6D-+IN-Pad12)") (class "Default")
      (node (ref "IC6") (pin "12") (pinfunction "+IN_12") (pintype "input"))
    )
    (net (code "100") (name "unconnected-(IC6D--IN-Pad13)") (class "Default")
      (node (ref "IC6") (pin "13") (pinfunction "-IN_13") (pintype "input"))
    )
    (net (code "101") (name "unconnected-(IC6D-OUT-Pad14)") (class "Default")
      (node (ref "IC6") (pin "14") (pinfunction "OUT_14") (pintype "output"))
    )
    (net (code "102") (name "unconnected-(IC7-RS-Pad8)") (class "Default")
      (node (ref "IC7") (pin "8") (pinfunction "RS_8") (pintype "input"))
    )
    (net (code "103") (name "unconnected-(IC7-VREF-Pad5)") (class "Default")
      (node (ref "IC7") (pin "5") (pinfunction "VREF_5") (pintype "output"))
    )
    (net (code "104") (name "unconnected-(IC8A-QH*-Pad9)") (class "Default")
      (node (ref "IC8") (pin "9") (pinfunction "QH*_9") (pintype "tri_state"))
    )
    (net (code "105") (name "unconnected-(J3-Pad2)") (class "Default")
      (node (ref "J3") (pin "2") (pinfunction "2_2") (pintype "passive"))
    )
    (net (code "106") (name "unconnected-(RN3B-2-Pad15)") (class "Default")
      (node (ref "RN3") (pin "15") (pinfunction "2_15") (pintype "passive"))
    )
    (net (code "107") (name "unconnected-(RN3C-2-Pad14)") (class "Default")
      (node (ref "RN3") (pin "14") (pinfunction "2_14") (pintype "passive"))
    )
    (net (code "108") (name "unconnected-(RN3D-2-Pad13)") (class "Default")
      (node (ref "RN3") (pin "13") (pinfunction "2_13") (pintype "passive"))
    )
    (net (code "109") (name "unconnected-(RN3E-2-Pad12)") (class "Default")
      (node (ref "RN3") (pin "12") (pinfunction "2_12") (pintype "passive"))
    )
    (net (code "110") (name "unconnected-(RN3F-2-Pad11)") (class "Default")
      (node (ref "RN3") (pin "11") (pinfunction "2_11") (pintype "passive"))
    )
    (net (code "111") (name "unconnected-(RN3G-2-Pad10)") (class "Default")
      (node (ref "RN3") (pin "10") (pinfunction "2_10") (pintype "passive"))
    )
    (net (code "112") (name "unconnected-(RN6B-2-Pad15)") (class "Default")
      (node (ref "RN6") (pin "15") (pinfunction "2_15") (pintype "passive"))
    )
    (net (code "113") (name "unconnected-(RN6C-2-Pad14)") (class "Default")
      (node (ref "RN6") (pin "14") (pinfunction "2_14") (pintype "passive"))
    )
    (net (code "114") (name "unconnected-(RN6D-2-Pad13)") (class "Default")
      (node (ref "RN6") (pin "13") (pinfunction "2_13") (pintype "passive"))
    )
    (net (code "115") (name "unconnected-(RN6E-2-Pad12)") (class "Default")
      (node (ref "RN6") (pin "12") (pinfunction "2_12") (pintype "passive"))
    )
    (net (code "116") (name "unconnected-(RN6F-2-Pad11)") (class "Default")
      (node (ref "RN6") (pin "11") (pinfunction "2_11") (pintype "passive"))
    )
    (net (code "117") (name "unconnected-(RN6G-2-Pad10)") (class "Default")
      (node (ref "RN6") (pin "10") (pinfunction "2_10") (pintype "passive"))
    )
    (net (code "118") (name "unconnected-(U$1A-1-PadA1-3V3)") (class "Default")
      (node (ref "U$1") (pin "A1-3V3") (pinfunction "1_A1-3V3") (pintype "passive"))
    )
    (net (code "119") (name "unconnected-(U$1A-3-PadA2-PB5)") (class "Default")
      (node (ref "U$1") (pin "A2-PB5") (pinfunction "3_A2-PB5") (pintype "passive"))
    )
    (net (code "120") (name "unconnected-(U$1A-5-PadA3-PB0)") (class "Default")
      (node (ref "U$1") (pin "A3-PB0") (pinfunction "5_A3-PB0") (pintype "passive"))
    )
    (net (code "121") (name "unconnected-(U$1A-6-PadB3-PD0)") (class "Default")
      (node (ref "U$1") (pin "B3-PD0") (pinfunction "6_B3-PD0") (pintype "passive"))
    )
    (net (code "122") (name "unconnected-(U$1A-7-PadA4-PB1)") (class "Default")
      (node (ref "U$1") (pin "A4-PB1") (pinfunction "7_A4-PB1") (pintype "passive"))
    )
    (net (code "123") (name "unconnected-(U$1A-8-PadB4-PD1)") (class "Default")
      (node (ref "U$1") (pin "B4-PD1") (pinfunction "8_B4-PD1") (pintype "passive"))
    )
    (net (code "124") (name "unconnected-(U$1A-10-PadB5-PD2)") (class "Default")
      (node (ref "U$1") (pin "B5-PD2") (pinfunction "10_B5-PD2") (pintype "passive"))
    )
    (net (code "125") (name "unconnected-(U$1A-12-PadB6-PD3)") (class "Default")
      (node (ref "U$1") (pin "B6-PD3") (pinfunction "12_B6-PD3") (pintype "passive"))
    )
    (net (code "126") (name "unconnected-(U$1A-14-PadB7-PE1)") (class "Default")
      (node (ref "U$1") (pin "B7-PE1") (pinfunction "14_B7-PE1") (pintype "passive"))
    )
    (net (code "127") (name "unconnected-(U$1A-16-PadB8-PE2)") (class "Default")
      (node (ref "U$1") (pin "B8-PE2") (pinfunction "16_B8-PE2") (pintype "passive"))
    )
    (net (code "128") (name "unconnected-(U$1A-17-PadA9-PA6)") (class "Default")
      (node (ref "U$1") (pin "A9-PA6") (pinfunction "17_A9-PA6") (pintype "passive"))
    )
    (net (code "129") (name "unconnected-(U$1A-18-PadB9-PE3)") (class "Default")
      (node (ref "U$1") (pin "B9-PE3") (pinfunction "18_B9-PE3") (pintype "passive"))
    )
    (net (code "130") (name "unconnected-(U$1A-19-PadA10-PA7)") (class "Default")
      (node (ref "U$1") (pin "A10-PA7") (pinfunction "19_A10-PA7") (pintype "passive"))
    )
    (net (code "131") (name "unconnected-(U$1A-20-PadB10-PF1)") (class "Default")
      (node (ref "U$1") (pin "B10-PF1") (pinfunction "20_B10-PF1") (pintype "passive"))
    )
    (net (code "132") (name "unconnected-(U$1B-1-PadC1-PF2)") (class "Default")
      (node (ref "U$1") (pin "C1-PF2") (pinfunction "1_C1-PF2") (pintype "passive"))
    )
    (net (code "133") (name "unconnected-(U$1B-3-PadC2-PF3)") (class "Default")
      (node (ref "U$1") (pin "C2-PF3") (pinfunction "3_C2-PF3") (pintype "passive"))
    )
    (net (code "134") (name "unconnected-(U$1B-4-PadD2-PB2)") (class "Default")
      (node (ref "U$1") (pin "D2-PB2") (pinfunction "4_D2-PB2") (pintype "passive"))
    )
    (net (code "135") (name "unconnected-(U$1B-5-PadC3-PB3)") (class "Default")
      (node (ref "U$1") (pin "C3-PB3") (pinfunction "5_C3-PB3") (pintype "passive"))
    )
    (net (code "136") (name "unconnected-(U$1B-7-PadC4-PC4)") (class "Default")
      (node (ref "U$1") (pin "C4-PC4") (pinfunction "7_C4-PC4") (pintype "passive"))
    )
    (net (code "137") (name "unconnected-(U$1B-8-PadD4-PF0)") (class "Default")
      (node (ref "U$1") (pin "D4-PF0") (pinfunction "8_D4-PF0") (pintype "passive"))
    )
    (net (code "138") (name "unconnected-(U$1B-9-PadC5-PC5)") (class "Default")
      (node (ref "U$1") (pin "C5-PC5") (pinfunction "9_C5-PC5") (pintype "passive"))
    )
    (net (code "139") (name "unconnected-(U$1B-10-PadD5-NRST)") (class "Default")
      (node (ref "U$1") (pin "D5-NRST") (pinfunction "10_D5-NRST") (pintype "passive"))
    )
    (net (code "140") (name "unconnected-(U$1B-11-PadC6-PC6)") (class "Default")
      (node (ref "U$1") (pin "C6-PC6") (pinfunction "11_C6-PC6") (pintype "passive"))
    )
    (net (code "141") (name "unconnected-(U$1B-13-PadC7-PC7)") (class "Default")
      (node (ref "U$1") (pin "C7-PC7") (pinfunction "13_C7-PC7") (pintype "passive"))
    )
    (net (code "142") (name "unconnected-(U$1B-15-PadC8-PD6)") (class "Default")
      (node (ref "U$1") (pin "C8-PD6") (pinfunction "15_C8-PD6") (pintype "passive"))
    )
    (net (code "143") (name "unconnected-(U$1B-17-PadC9-PD7)") (class "Default")
      (node (ref "U$1") (pin "C9-PD7") (pinfunction "17_C9-PD7") (pintype "passive"))
    )
    (net (code "144") (name "unconnected-(U$1B-19-PadC10-PF4)") (class "Default")
      (node (ref "U$1") (pin "C10-PF4") (pinfunction "19_C10-PF4") (pintype "passive"))
    )
    (net (code "145") (name "unconnected-(U$1B-20-PadD10-PA2)") (class "Default")
      (node (ref "U$1") (pin "D10-PA2") (pinfunction "20_D10-PA2") (pintype "passive"))
    )
    (net (code "146") (name "unconnected-(X1-Pad1)") (class "Default")
      (node (ref "X1") (pin "1") (pinfunction "1_1") (pintype "passive"))
    )
    (net (code "147") (name "unconnected-(X2-Pad1)") (class "Default")
      (node (ref "X2") (pin "1") (pinfunction "1_1") (pintype "passive"))
    )
    (net (code "148") (name "unconnected-(X2C-1-Pad3)") (class "Default")
      (node (ref "X2") (pin "3") (pinfunction "1_3") (pintype "passive"))
    )
    (net (code "149") (name "unconnected-(X2D-1-Pad4)") (class "Default")
      (node (ref "X2") (pin "4") (pinfunction "1_4") (pintype "passive"))
    )
    (net (code "150") (name "unconnected-(X2E-1-Pad5)") (class "Default")
      (node (ref "X2") (pin "5") (pinfunction "1_5") (pintype "passive"))
    )
    (net (code "151") (name "unconnected-(X2F-1-Pad6)") (class "Default")
      (node (ref "X2") (pin "6") (pinfunction "1_6") (pintype "passive"))
    )
    (net (code "152") (name "unconnected-(X2G-1-Pad7)") (class "Default")
      (node (ref "X2") (pin "7") (pinfunction "1_7") (pintype "passive"))
    )
    (net (code "153") (name "unconnected-(X2H-1-Pad8)") (class "Default")
      (node (ref "X2") (pin "8") (pinfunction "1_8") (pintype "passive"))
    )
    (net (code "154") (name "unconnected-(X3-Pad1)") (class "Default")
      (node (ref "X3") (pin "1") (pinfunction "1_1") (pintype "passive"))
    )
    (net (code "155") (name "unconnected-(X4-Pad1)") (class "Default")
      (node (ref "X4") (pin "1") (pinfunction "1_1") (pintype "passive"))
    )
    (net (code "156") (name "unconnected-(X4C-1-Pad3)") (class "Default")
      (node (ref "X4") (pin "3") (pinfunction "1_3") (pintype "passive"))
    )
    (net (code "157") (name "unconnected-(X4D-1-Pad4)") (class "Default")
      (node (ref "X4") (pin "4") (pinfunction "1_4") (pintype "passive"))
    )
    (net (code "158") (name "unconnected-(X4E-1-Pad5)") (class "Default")
      (node (ref "X4") (pin "5") (pinfunction "1_5") (pintype "passive"))
    )
    (net (code "159") (name "unconnected-(X4F-1-Pad6)") (class "Default")
      (node (ref "X4") (pin "6") (pinfunction "1_6") (pintype "passive"))
    )
    (net (code "160") (name "unconnected-(X4G-1-Pad7)") (class "Default")
      (node (ref "X4") (pin "7") (pinfunction "1_7") (pintype "passive"))
    )
    (net (code "161") (name "unconnected-(X4H-1-Pad8)") (class "Default")
      (node (ref "X4") (pin "8") (pinfunction "1_8") (pintype "passive"))
    )
  )
)
